# Motherboard.net
KiCad netlist of a schematic drawn in EAGLE
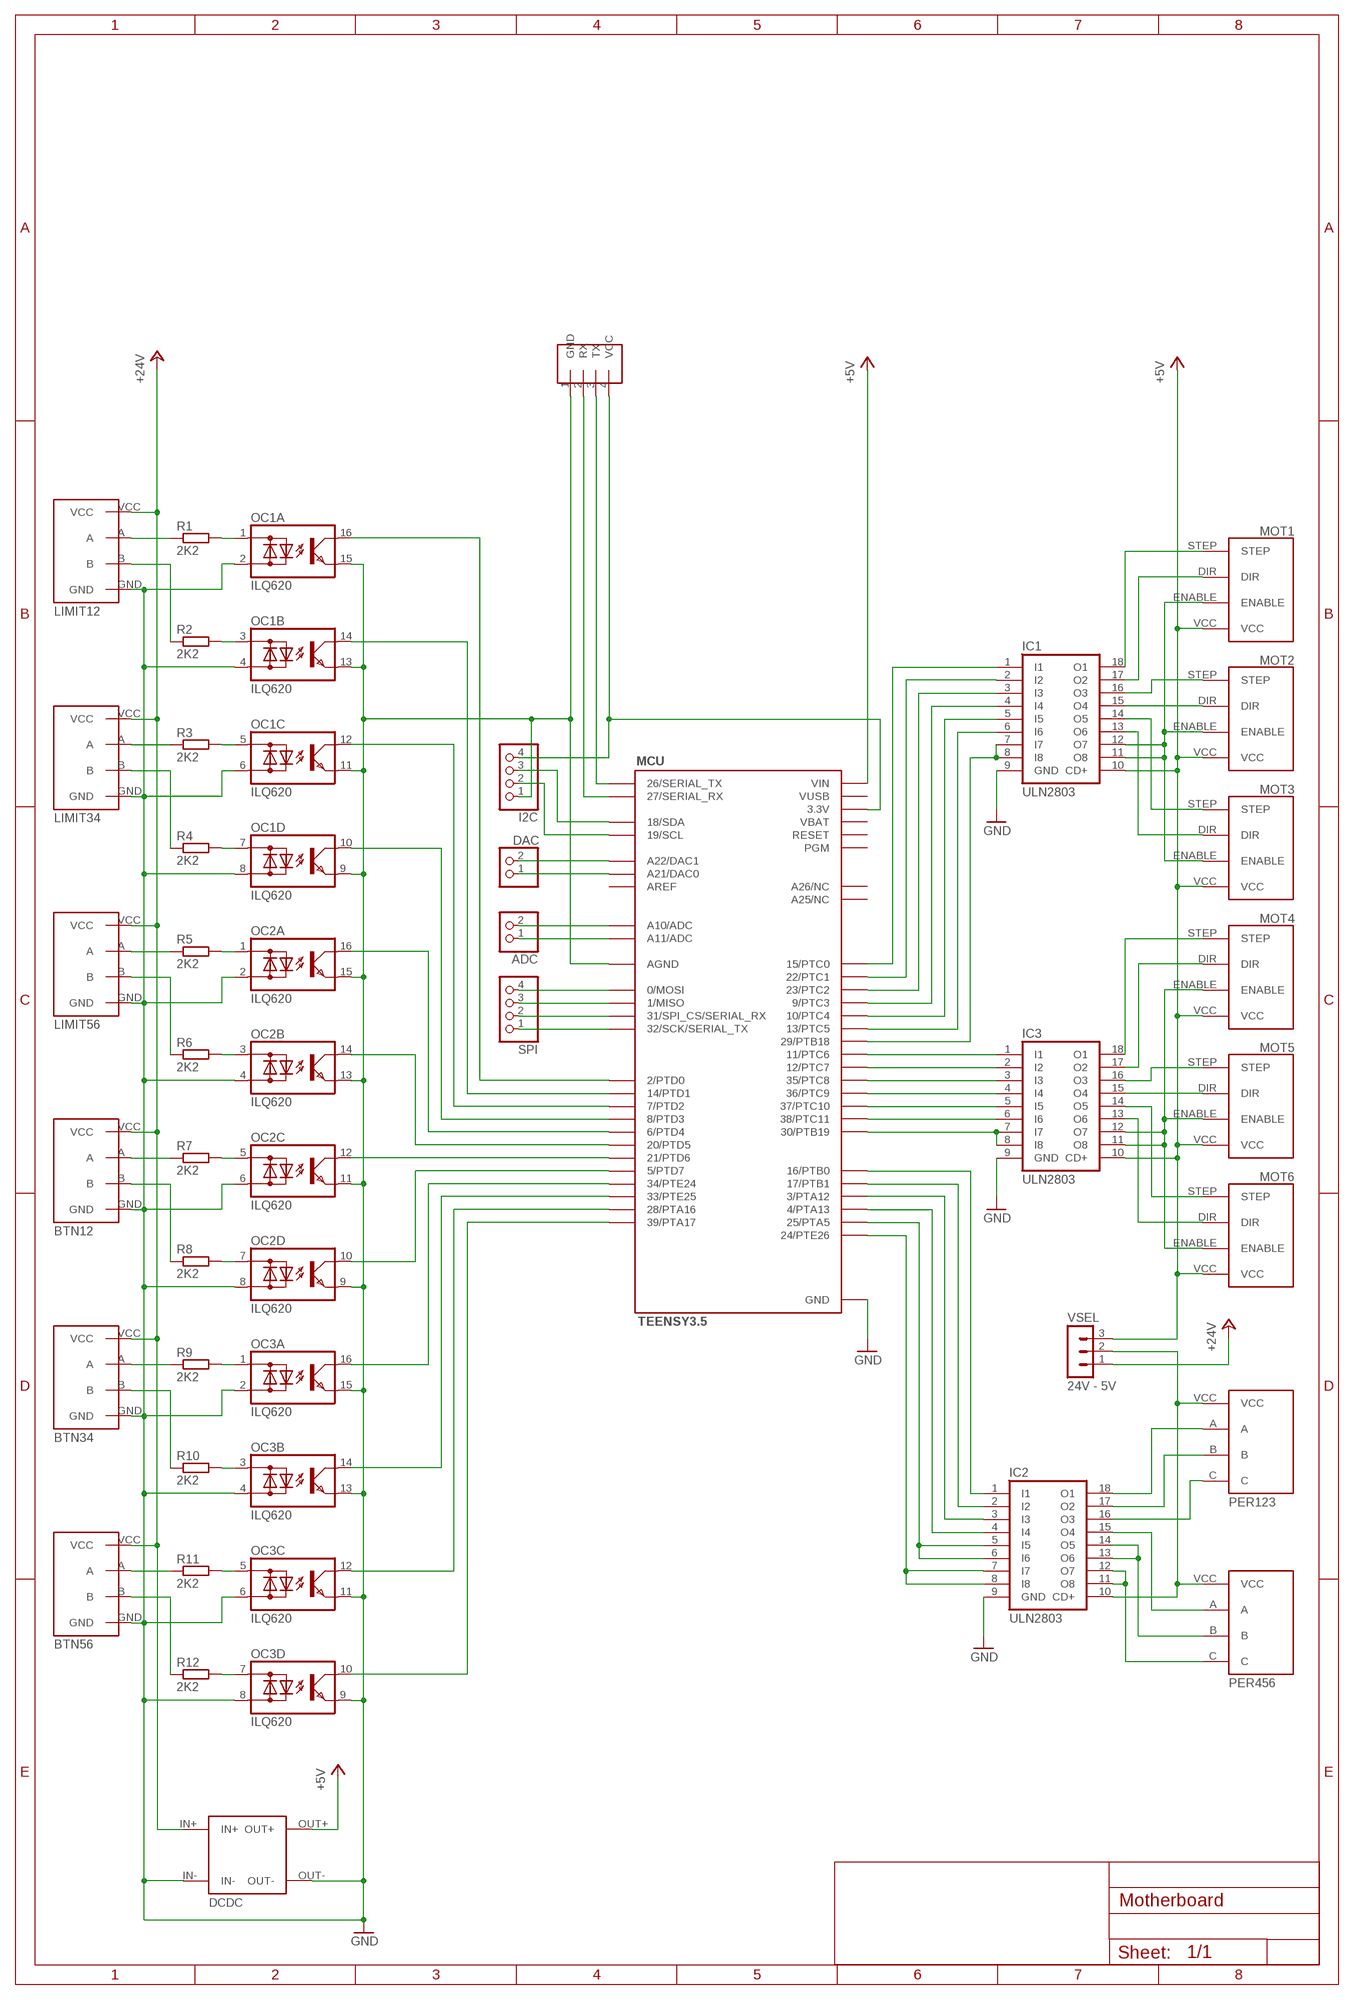
[diagram p0: schematic, sheet 1]

(export (version "E")
  (design (tool "Eeschema 10.0.6"))
  (components
    (comp (ref "ADC")
      (value "PINHD-1X2")
      (footprint "eagle-import:1X02")
      (libsource (lib "eagle-import") (part "PINHD-1X2"))
    )
    (comp (ref "BTN12")
      (value "CONN4B")
      (footprint "eagle-import:CONN4B")
      (libsource (lib "eagle-import") (part "CONN4B"))
    )
    (comp (ref "BTN34")
      (value "CONN4B")
      (footprint "eagle-import:CONN4B")
      (libsource (lib "eagle-import") (part "CONN4B"))
    )
    (comp (ref "BTN56")
      (value "CONN4B")
      (footprint "eagle-import:CONN4B")
      (libsource (lib "eagle-import") (part "CONN4B"))
    )
    (comp (ref "DAC")
      (value "PINHD-1X2")
      (footprint "eagle-import:1X02")
      (libsource (lib "eagle-import") (part "PINHD-1X2"))
    )
    (comp (ref "DCDC")
      (value "DCDC")
      (footprint "eagle-import:DCDC")
      (libsource (lib "eagle-import") (part "DCDC"))
    )
    (comp (ref "I2C")
      (value "PINHD-1X4")
      (footprint "eagle-import:1X04")
      (libsource (lib "eagle-import") (part "PINHD-1X4"))
    )
    (comp (ref "IC1")
      (value "ULN2803")
      (footprint "eagle-import:DIL18")
      (libsource (lib "eagle-import") (part "ULN2803A"))
    )
    (comp (ref "IC2")
      (value "ULN2803")
      (footprint "eagle-import:DIL18")
      (libsource (lib "eagle-import") (part "ULN2803A"))
    )
    (comp (ref "IC3")
      (value "ULN2803")
      (footprint "eagle-import:DIL18")
      (libsource (lib "eagle-import") (part "ULN2803A"))
    )
    (comp (ref "LIMIT12")
      (value "CONN4B")
      (footprint "eagle-import:CONN4B")
      (libsource (lib "eagle-import") (part "CONN4B"))
    )
    (comp (ref "LIMIT34")
      (value "CONN4B")
      (footprint "eagle-import:CONN4B")
      (libsource (lib "eagle-import") (part "CONN4B"))
    )
    (comp (ref "LIMIT56")
      (value "CONN4B")
      (footprint "eagle-import:CONN4B")
      (libsource (lib "eagle-import") (part "CONN4B"))
    )
    (comp (ref "MCU")
      (value "TEENSY3.5")
      (footprint "eagle-import:TEENSY_3.5_ALL_PINS")
      (libsource (lib "eagle-import") (part "TEENSY_3.5_ALL_PINS"))
    )
    (comp (ref "MOT1")
      (value "CONN4")
      (footprint "eagle-import:CONN4")
      (libsource (lib "eagle-import") (part "CONN4"))
    )
    (comp (ref "MOT2")
      (value "CONN4")
      (footprint "eagle-import:CONN4")
      (libsource (lib "eagle-import") (part "CONN4"))
    )
    (comp (ref "MOT3")
      (value "CONN4")
      (footprint "eagle-import:CONN4")
      (libsource (lib "eagle-import") (part "CONN4"))
    )
    (comp (ref "MOT4")
      (value "CONN4")
      (footprint "eagle-import:CONN4")
      (libsource (lib "eagle-import") (part "CONN4"))
    )
    (comp (ref "MOT5")
      (value "CONN4")
      (footprint "eagle-import:CONN4")
      (libsource (lib "eagle-import") (part "CONN4"))
    )
    (comp (ref "MOT6")
      (value "CONN4")
      (footprint "eagle-import:CONN4")
      (libsource (lib "eagle-import") (part "CONN4"))
    )
    (comp (ref "OC1")
      (value "ILQ620")
      (footprint "eagle-import:DIL16")
      (libsource (lib "eagle-import") (part "ILQ620"))
    )
    (comp (ref "OC2")
      (value "ILQ620")
      (footprint "eagle-import:DIL16")
      (libsource (lib "eagle-import") (part "ILQ620"))
    )
    (comp (ref "OC3")
      (value "ILQ620")
      (footprint "eagle-import:DIL16")
      (libsource (lib "eagle-import") (part "ILQ620"))
    )
    (comp (ref "PER123")
      (value "CONN4C")
      (footprint "eagle-import:CONN4C")
      (libsource (lib "eagle-import") (part "CONN4C"))
    )
    (comp (ref "PER456")
      (value "CONN4C")
      (footprint "eagle-import:CONN4C")
      (libsource (lib "eagle-import") (part "CONN4C"))
    )
    (comp (ref "R1")
      (value "2K2")
      (footprint "eagle-import:0207_10")
      (libsource (lib "eagle-import") (part "R-EU_0207/10"))
    )
    (comp (ref "R2")
      (value "2K2")
      (footprint "eagle-import:0207_10")
      (libsource (lib "eagle-import") (part "R-EU_0207/10"))
    )
    (comp (ref "R3")
      (value "2K2")
      (footprint "eagle-import:0207_10")
      (libsource (lib "eagle-import") (part "R-EU_0207/10"))
    )
    (comp (ref "R4")
      (value "2K2")
      (footprint "eagle-import:0207_10")
      (libsource (lib "eagle-import") (part "R-EU_0207/10"))
    )
    (comp (ref "R5")
      (value "2K2")
      (footprint "eagle-import:0207_10")
      (libsource (lib "eagle-import") (part "R-EU_0207/10"))
    )
    (comp (ref "R6")
      (value "2K2")
      (footprint "eagle-import:0207_10")
      (libsource (lib "eagle-import") (part "R-EU_0207/10"))
    )
    (comp (ref "R7")
      (value "2K2")
      (footprint "eagle-import:0207_10")
      (libsource (lib "eagle-import") (part "R-EU_0207/10"))
    )
    (comp (ref "R8")
      (value "2K2")
      (footprint "eagle-import:0207_10")
      (libsource (lib "eagle-import") (part "R-EU_0207/10"))
    )
    (comp (ref "R9")
      (value "2K2")
      (footprint "eagle-import:0207_10")
      (libsource (lib "eagle-import") (part "R-EU_0207/10"))
    )
    (comp (ref "R10")
      (value "2K2")
      (footprint "eagle-import:0207_10")
      (libsource (lib "eagle-import") (part "R-EU_0207/10"))
    )
    (comp (ref "R11")
      (value "2K2")
      (footprint "eagle-import:0207_10")
      (libsource (lib "eagle-import") (part "R-EU_0207/10"))
    )
    (comp (ref "R12")
      (value "2K2")
      (footprint "eagle-import:0207_10")
      (libsource (lib "eagle-import") (part "R-EU_0207/10"))
    )
    (comp (ref "SPI")
      (value "PINHD-1X4")
      (footprint "eagle-import:1X04")
      (libsource (lib "eagle-import") (part "PINHD-1X4"))
    )
    (comp (ref "U$1")
      (value "SERIAL-SUBD9-IF")
      (footprint "eagle-import:SERIAL-SUBD9-IF")
      (libsource (lib "eagle-import") (part "SERIAL-SUBD9-IF"))
    )
    (comp (ref "VSEL")
      (value "24V - 5V")
      (footprint "eagle-import:MA03-1")
      (libsource (lib "eagle-import") (part "MA03-1"))
    )
  )
  (nets
    (net (code "1") (name "+5V") (class "Default")
      (node (ref "DCDC") (pin "OUT+") (pinfunction "OUT+_OUT+") (pintype "power_in"))
      (node (ref "IC1") (pin "10") (pinfunction "CD+_10") (pintype "passive"))
      (node (ref "IC3") (pin "10") (pinfunction "CD+_10") (pintype "passive"))
      (node (ref "MCU") (pin "VIN") (pinfunction "VIN_VIN") (pintype "power_in"))
      (node (ref "MOT1") (pin "VCC") (pinfunction "VCC_VCC") (pintype "power_in"))
      (node (ref "MOT2") (pin "VCC") (pinfunction "VCC_VCC") (pintype "power_in"))
      (node (ref "MOT3") (pin "VCC") (pinfunction "VCC_VCC") (pintype "power_in"))
      (node (ref "MOT4") (pin "VCC") (pinfunction "VCC_VCC") (pintype "power_in"))
      (node (ref "MOT5") (pin "VCC") (pinfunction "VCC_VCC") (pintype "power_in"))
      (node (ref "MOT6") (pin "VCC") (pinfunction "VCC_VCC") (pintype "power_in"))
      (node (ref "VSEL") (pin "3") (pinfunction "3_3") (pintype "passive"))
    )
    (net (code "2") (name "+24V") (class "Default")
      (node (ref "BTN12") (pin "VCC") (pinfunction "VCC_VCC") (pintype "power_in"))
      (node (ref "BTN34") (pin "VCC") (pinfunction "VCC_VCC") (pintype "power_in"))
      (node (ref "BTN56") (pin "VCC") (pinfunction "VCC_VCC") (pintype "power_in"))
      (node (ref "DCDC") (pin "IN+") (pinfunction "IN+_IN+") (pintype "power_in"))
      (node (ref "LIMIT12") (pin "VCC") (pinfunction "VCC_VCC") (pintype "power_in"))
      (node (ref "LIMIT34") (pin "VCC") (pinfunction "VCC_VCC") (pintype "power_in"))
      (node (ref "LIMIT56") (pin "VCC") (pinfunction "VCC_VCC") (pintype "power_in"))
      (node (ref "VSEL") (pin "1") (pinfunction "1_1") (pintype "passive"))
    )
    (net (code "3") (name "/AREF") (class "Default")
      (node (ref "MCU") (pin "AREF") (pinfunction "AREF_AREF") (pintype "power_in"))
    )
    (net (code "4") (name "/VBAT") (class "Default")
      (node (ref "MCU") (pin "VBAT") (pinfunction "VBAT_VBAT") (pintype "power_in"))
    )
    (net (code "5") (name "/VUSB") (class "Default")
      (node (ref "MCU") (pin "VUSB") (pinfunction "VUSB_VUSB") (pintype "power_in"))
    )
    (net (code "6") (name "GND") (class "Default")
      (node (ref "BTN12") (pin "GND") (pinfunction "GND_GND") (pintype "power_in"))
      (node (ref "BTN34") (pin "GND") (pinfunction "GND_GND") (pintype "power_in"))
      (node (ref "BTN56") (pin "GND") (pinfunction "GND_GND") (pintype "power_in"))
      (node (ref "DCDC") (pin "IN-") (pinfunction "IN-_IN-") (pintype "power_in"))
      (node (ref "DCDC") (pin "OUT-") (pinfunction "OUT-_OUT-") (pintype "bidirectional"))
      (node (ref "I2C") (pin "1") (pinfunction "1_1") (pintype "passive"))
      (node (ref "IC1") (pin "9") (pinfunction "GND_9") (pintype "power_in"))
      (node (ref "IC2") (pin "9") (pinfunction "GND_9") (pintype "power_in"))
      (node (ref "IC3") (pin "9") (pinfunction "GND_9") (pintype "power_in"))
      (node (ref "LIMIT12") (pin "GND") (pinfunction "GND_GND") (pintype "power_in"))
      (node (ref "LIMIT34") (pin "GND") (pinfunction "GND_GND") (pintype "power_in"))
      (node (ref "LIMIT56") (pin "GND") (pinfunction "GND_GND") (pintype "power_in"))
      (node (ref "MCU") (pin "AGND") (pinfunction "AGND_AGND") (pintype "power_in"))
      (node (ref "MCU") (pin "GND") (pinfunction "GND_GND") (pintype "power_in"))
      (node (ref "MCU") (pin "GND1") (pinfunction "GND_GND1") (pintype "power_in"))
      (node (ref "MCU") (pin "GND3") (pinfunction "GND_GND3") (pintype "power_in"))
      (node (ref "MCU") (pin "GND4") (pinfunction "GND_GND4") (pintype "power_in"))
      (node (ref "MCU") (pin "GND6") (pinfunction "GND_GND6") (pintype "power_in"))
      (node (ref "OC1") (pin "11") (pinfunction "E_11") (pintype "passive"))
      (node (ref "OC1") (pin "13") (pinfunction "E_13") (pintype "passive"))
      (node (ref "OC1") (pin "15") (pinfunction "E_15") (pintype "passive"))
      (node (ref "OC1") (pin "2") (pinfunction "AC2_2") (pintype "passive"))
      (node (ref "OC1") (pin "4") (pinfunction "AC2_4") (pintype "passive"))
      (node (ref "OC1") (pin "6") (pinfunction "AC2_6") (pintype "passive"))
      (node (ref "OC1") (pin "8") (pinfunction "AC2_8") (pintype "passive"))
      (node (ref "OC1") (pin "9") (pinfunction "E_9") (pintype "passive"))
      (node (ref "OC2") (pin "11") (pinfunction "E_11") (pintype "passive"))
      (node (ref "OC2") (pin "13") (pinfunction "E_13") (pintype "passive"))
      (node (ref "OC2") (pin "15") (pinfunction "E_15") (pintype "passive"))
      (node (ref "OC2") (pin "2") (pinfunction "AC2_2") (pintype "passive"))
      (node (ref "OC2") (pin "4") (pinfunction "AC2_4") (pintype "passive"))
      (node (ref "OC2") (pin "6") (pinfunction "AC2_6") (pintype "passive"))
      (node (ref "OC2") (pin "8") (pinfunction "AC2_8") (pintype "passive"))
      (node (ref "OC2") (pin "9") (pinfunction "E_9") (pintype "passive"))
      (node (ref "OC3") (pin "11") (pinfunction "E_11") (pintype "passive"))
      (node (ref "OC3") (pin "13") (pinfunction "E_13") (pintype "passive"))
      (node (ref "OC3") (pin "15") (pinfunction "E_15") (pintype "passive"))
      (node (ref "OC3") (pin "2") (pinfunction "AC2_2") (pintype "passive"))
      (node (ref "OC3") (pin "4") (pinfunction "AC2_4") (pintype "passive"))
      (node (ref "OC3") (pin "6") (pinfunction "AC2_6") (pintype "passive"))
      (node (ref "OC3") (pin "8") (pinfunction "AC2_8") (pintype "passive"))
      (node (ref "OC3") (pin "9") (pinfunction "E_9") (pintype "passive"))
      (node (ref "U$1") (pin "1") (pinfunction "GND_1") (pintype "power_in"))
    )
    (net (code "7") (name "Net-(BTN12-PadA)") (class "Default")
      (node (ref "BTN12") (pin "A") (pinfunction "A_A") (pintype "bidirectional"))
      (node (ref "R7") (pin "1") (pinfunction "1_1") (pintype "passive"))
    )
    (net (code "8") (name "Net-(BTN12-PadB)") (class "Default")
      (node (ref "BTN12") (pin "B") (pinfunction "B_B") (pintype "bidirectional"))
      (node (ref "R8") (pin "1") (pinfunction "1_1") (pintype "passive"))
    )
    (net (code "9") (name "Net-(BTN34-PadA)") (class "Default")
      (node (ref "BTN34") (pin "A") (pinfunction "A_A") (pintype "bidirectional"))
      (node (ref "R9") (pin "1") (pinfunction "1_1") (pintype "passive"))
    )
    (net (code "10") (name "Net-(BTN34-PadB)") (class "Default")
      (node (ref "BTN34") (pin "B") (pinfunction "B_B") (pintype "bidirectional"))
      (node (ref "R10") (pin "1") (pinfunction "1_1") (pintype "passive"))
    )
    (net (code "11") (name "Net-(BTN56-PadA)") (class "Default")
      (node (ref "BTN56") (pin "A") (pinfunction "A_A") (pintype "bidirectional"))
      (node (ref "R11") (pin "1") (pinfunction "1_1") (pintype "passive"))
    )
    (net (code "12") (name "Net-(BTN56-PadB)") (class "Default")
      (node (ref "BTN56") (pin "B") (pinfunction "B_B") (pintype "bidirectional"))
      (node (ref "R12") (pin "1") (pinfunction "1_1") (pintype "passive"))
    )
    (net (code "13") (name "Net-(IC1-I1)") (class "Default")
      (node (ref "IC1") (pin "1") (pinfunction "I1_1") (pintype "input"))
      (node (ref "MCU") (pin "15/A1") (pinfunction "15/PTC0_15/A1") (pintype "bidirectional"))
    )
    (net (code "14") (name "Net-(IC1-I2)") (class "Default")
      (node (ref "IC1") (pin "2") (pinfunction "I2_2") (pintype "input"))
      (node (ref "MCU") (pin "22/A8") (pinfunction "22/PTC1_22/A8") (pintype "bidirectional"))
    )
    (net (code "15") (name "Net-(IC1-I3)") (class "Default")
      (node (ref "IC1") (pin "3") (pinfunction "I3_3") (pintype "input"))
      (node (ref "MCU") (pin "23/A9") (pinfunction "23/PTC2_23/A9") (pintype "bidirectional"))
    )
    (net (code "16") (name "Net-(IC1-I4)") (class "Default")
      (node (ref "IC1") (pin "4") (pinfunction "I4_4") (pintype "input"))
      (node (ref "MCU") (pin "9") (pinfunction "9/PTC3_9") (pintype "bidirectional"))
    )
    (net (code "17") (name "Net-(IC1-I5)") (class "Default")
      (node (ref "IC1") (pin "5") (pinfunction "I5_5") (pintype "input"))
      (node (ref "MCU") (pin "10") (pinfunction "10/PTC4_10") (pintype "bidirectional"))
    )
    (net (code "18") (name "Net-(IC1-I6)") (class "Default")
      (node (ref "IC1") (pin "6") (pinfunction "I6_6") (pintype "input"))
      (node (ref "MCU") (pin "13") (pinfunction "13/PTC5_13") (pintype "bidirectional"))
    )
    (net (code "19") (name "Net-(IC1-I7)") (class "Default")
      (node (ref "IC1") (pin "7") (pinfunction "I7_7") (pintype "input"))
      (node (ref "IC1") (pin "8") (pinfunction "I8_8") (pintype "input"))
      (node (ref "MCU") (pin "29") (pinfunction "29/PTB18_29") (pintype "bidirectional"))
    )
    (net (code "20") (name "Net-(IC1-O1)") (class "Default")
      (node (ref "IC1") (pin "18") (pinfunction "O1_18") (pintype "open_collector"))
      (node (ref "MOT1") (pin "STEP") (pinfunction "STEP_STEP") (pintype "bidirectional"))
    )
    (net (code "21") (name "Net-(IC1-O2)") (class "Default")
      (node (ref "IC1") (pin "17") (pinfunction "O2_17") (pintype "open_collector"))
      (node (ref "MOT1") (pin "DIR") (pinfunction "DIR_DIR") (pintype "bidirectional"))
    )
    (net (code "22") (name "Net-(IC1-O3)") (class "Default")
      (node (ref "IC1") (pin "16") (pinfunction "O3_16") (pintype "open_collector"))
      (node (ref "MOT2") (pin "STEP") (pinfunction "STEP_STEP") (pintype "bidirectional"))
    )
    (net (code "23") (name "Net-(IC1-O4)") (class "Default")
      (node (ref "IC1") (pin "15") (pinfunction "O4_15") (pintype "open_collector"))
      (node (ref "MOT2") (pin "DIR") (pinfunction "DIR_DIR") (pintype "bidirectional"))
    )
    (net (code "24") (name "Net-(IC1-O5)") (class "Default")
      (node (ref "IC1") (pin "14") (pinfunction "O5_14") (pintype "open_collector"))
      (node (ref "MOT3") (pin "STEP") (pinfunction "STEP_STEP") (pintype "bidirectional"))
    )
    (net (code "25") (name "Net-(IC1-O6)") (class "Default")
      (node (ref "IC1") (pin "13") (pinfunction "O6_13") (pintype "open_collector"))
      (node (ref "MOT3") (pin "DIR") (pinfunction "DIR_DIR") (pintype "bidirectional"))
    )
    (net (code "26") (name "Net-(IC1-O7)") (class "Default")
      (node (ref "IC1") (pin "11") (pinfunction "O8_11") (pintype "open_collector"))
      (node (ref "IC1") (pin "12") (pinfunction "O7_12") (pintype "open_collector"))
      (node (ref "MOT1") (pin "ENABLE") (pinfunction "ENABLE_ENABLE") (pintype "bidirectional"))
      (node (ref "MOT2") (pin "ENABLE") (pinfunction "ENABLE_ENABLE") (pintype "bidirectional"))
      (node (ref "MOT3") (pin "ENABLE") (pinfunction "ENABLE_ENABLE") (pintype "bidirectional"))
    )
    (net (code "27") (name "Net-(IC2-CD+)") (class "Default")
      (node (ref "IC2") (pin "10") (pinfunction "CD+_10") (pintype "passive"))
      (node (ref "PER123") (pin "VCC") (pinfunction "VCC_VCC") (pintype "power_in"))
      (node (ref "PER456") (pin "VCC") (pinfunction "VCC_VCC") (pintype "power_in"))
      (node (ref "VSEL") (pin "2") (pinfunction "2_2") (pintype "passive"))
    )
    (net (code "28") (name "Net-(IC2-I1)") (class "Default")
      (node (ref "IC2") (pin "1") (pinfunction "I1_1") (pintype "input"))
      (node (ref "MCU") (pin "16/A2") (pinfunction "16/PTB0_16/A2") (pintype "bidirectional"))
    )
    (net (code "29") (name "Net-(IC2-I2)") (class "Default")
      (node (ref "IC2") (pin "2") (pinfunction "I2_2") (pintype "input"))
      (node (ref "MCU") (pin "17/A3") (pinfunction "17/PTB1_17/A3") (pintype "bidirectional"))
    )
    (net (code "30") (name "Net-(IC2-I3)") (class "Default")
      (node (ref "IC2") (pin "3") (pinfunction "I3_3") (pintype "input"))
      (node (ref "MCU") (pin "3") (pinfunction "3/PTA12_3") (pintype "bidirectional"))
    )
    (net (code "31") (name "Net-(IC2-I4)") (class "Default")
      (node (ref "IC2") (pin "4") (pinfunction "I4_4") (pintype "input"))
      (node (ref "MCU") (pin "4") (pinfunction "4/PTA13_4") (pintype "bidirectional"))
    )
    (net (code "32") (name "Net-(IC2-I5)") (class "Default")
      (node (ref "IC2") (pin "5") (pinfunction "I5_5") (pintype "input"))
      (node (ref "IC2") (pin "6") (pinfunction "I6_6") (pintype "input"))
      (node (ref "MCU") (pin "25") (pinfunction "25/PTA5_25") (pintype "bidirectional"))
    )
    (net (code "33") (name "Net-(IC2-I7)") (class "Default")
      (node (ref "IC2") (pin "7") (pinfunction "I7_7") (pintype "input"))
      (node (ref "IC2") (pin "8") (pinfunction "I8_8") (pintype "input"))
      (node (ref "MCU") (pin "24") (pinfunction "24/PTE26_24") (pintype "bidirectional"))
    )
    (net (code "34") (name "Net-(IC2-O1)") (class "Default")
      (node (ref "IC2") (pin "18") (pinfunction "O1_18") (pintype "open_collector"))
      (node (ref "PER123") (pin "A") (pinfunction "A_A") (pintype "bidirectional"))
    )
    (net (code "35") (name "Net-(IC2-O2)") (class "Default")
      (node (ref "IC2") (pin "17") (pinfunction "O2_17") (pintype "open_collector"))
      (node (ref "PER123") (pin "B") (pinfunction "B_B") (pintype "bidirectional"))
    )
    (net (code "36") (name "Net-(IC2-O3)") (class "Default")
      (node (ref "IC2") (pin "16") (pinfunction "O3_16") (pintype "open_collector"))
      (node (ref "PER123") (pin "C") (pinfunction "C_C") (pintype "bidirectional"))
    )
    (net (code "37") (name "Net-(IC2-O4)") (class "Default")
      (node (ref "IC2") (pin "15") (pinfunction "O4_15") (pintype "open_collector"))
      (node (ref "PER456") (pin "A") (pinfunction "A_A") (pintype "bidirectional"))
    )
    (net (code "38") (name "Net-(IC2-O5)") (class "Default")
      (node (ref "IC2") (pin "13") (pinfunction "O6_13") (pintype "open_collector"))
      (node (ref "IC2") (pin "14") (pinfunction "O5_14") (pintype "open_collector"))
      (node (ref "PER456") (pin "B") (pinfunction "B_B") (pintype "bidirectional"))
    )
    (net (code "39") (name "Net-(IC2-O7)") (class "Default")
      (node (ref "IC2") (pin "11") (pinfunction "O8_11") (pintype "open_collector"))
      (node (ref "IC2") (pin "12") (pinfunction "O7_12") (pintype "open_collector"))
      (node (ref "PER456") (pin "C") (pinfunction "C_C") (pintype "bidirectional"))
    )
    (net (code "40") (name "Net-(IC3-I1)") (class "Default")
      (node (ref "IC3") (pin "1") (pinfunction "I1_1") (pintype "input"))
      (node (ref "MCU") (pin "11") (pinfunction "11/PTC6_11") (pintype "bidirectional"))
    )
    (net (code "41") (name "Net-(IC3-I2)") (class "Default")
      (node (ref "IC3") (pin "2") (pinfunction "I2_2") (pintype "input"))
      (node (ref "MCU") (pin "12") (pinfunction "12/PTC7_12") (pintype "bidirectional"))
    )
    (net (code "42") (name "Net-(IC3-I3)") (class "Default")
      (node (ref "IC3") (pin "3") (pinfunction "I3_3") (pintype "input"))
      (node (ref "MCU") (pin "35/A16") (pinfunction "35/PTC8_35/A16") (pintype "bidirectional"))
    )
    (net (code "43") (name "Net-(IC3-I4)") (class "Default")
      (node (ref "IC3") (pin "4") (pinfunction "I4_4") (pintype "input"))
      (node (ref "MCU") (pin "36/A17") (pinfunction "36/PTC9_36/A17") (pintype "bidirectional"))
    )
    (net (code "44") (name "Net-(IC3-I5)") (class "Default")
      (node (ref "IC3") (pin "5") (pinfunction "I5_5") (pintype "input"))
      (node (ref "MCU") (pin "37/A18") (pinfunction "37/PTC10_37/A18") (pintype "bidirectional"))
    )
    (net (code "45") (name "Net-(IC3-I6)") (class "Default")
      (node (ref "IC3") (pin "6") (pinfunction "I6_6") (pintype "input"))
      (node (ref "MCU") (pin "38/A19") (pinfunction "38/PTC11_38/A19") (pintype "bidirectional"))
    )
    (net (code "46") (name "Net-(IC3-I7)") (class "Default")
      (node (ref "IC3") (pin "7") (pinfunction "I7_7") (pintype "input"))
      (node (ref "IC3") (pin "8") (pinfunction "I8_8") (pintype "input"))
      (node (ref "MCU") (pin "30") (pinfunction "30/PTB19_30") (pintype "bidirectional"))
    )
    (net (code "47") (name "Net-(IC3-O1)") (class "Default")
      (node (ref "IC3") (pin "18") (pinfunction "O1_18") (pintype "open_collector"))
      (node (ref "MOT4") (pin "STEP") (pinfunction "STEP_STEP") (pintype "bidirectional"))
    )
    (net (code "48") (name "Net-(IC3-O2)") (class "Default")
      (node (ref "IC3") (pin "17") (pinfunction "O2_17") (pintype "open_collector"))
      (node (ref "MOT4") (pin "DIR") (pinfunction "DIR_DIR") (pintype "bidirectional"))
    )
    (net (code "49") (name "Net-(IC3-O3)") (class "Default")
      (node (ref "IC3") (pin "16") (pinfunction "O3_16") (pintype "open_collector"))
      (node (ref "MOT5") (pin "STEP") (pinfunction "STEP_STEP") (pintype "bidirectional"))
    )
    (net (code "50") (name "Net-(IC3-O4)") (class "Default")
      (node (ref "IC3") (pin "15") (pinfunction "O4_15") (pintype "open_collector"))
      (node (ref "MOT5") (pin "DIR") (pinfunction "DIR_DIR") (pintype "bidirectional"))
    )
    (net (code "51") (name "Net-(IC3-O5)") (class "Default")
      (node (ref "IC3") (pin "14") (pinfunction "O5_14") (pintype "open_collector"))
      (node (ref "MOT6") (pin "STEP") (pinfunction "STEP_STEP") (pintype "bidirectional"))
    )
    (net (code "52") (name "Net-(IC3-O6)") (class "Default")
      (node (ref "IC3") (pin "13") (pinfunction "O6_13") (pintype "open_collector"))
      (node (ref "MOT6") (pin "DIR") (pinfunction "DIR_DIR") (pintype "bidirectional"))
    )
    (net (code "53") (name "Net-(IC3-O7)") (class "Default")
      (node (ref "IC3") (pin "11") (pinfunction "O8_11") (pintype "open_collector"))
      (node (ref "IC3") (pin "12") (pinfunction "O7_12") (pintype "open_collector"))
      (node (ref "MOT4") (pin "ENABLE") (pinfunction "ENABLE_ENABLE") (pintype "bidirectional"))
      (node (ref "MOT5") (pin "ENABLE") (pinfunction "ENABLE_ENABLE") (pintype "bidirectional"))
      (node (ref "MOT6") (pin "ENABLE") (pinfunction "ENABLE_ENABLE") (pintype "bidirectional"))
    )
    (net (code "54") (name "Net-(LIMIT12-PadA)") (class "Default")
      (node (ref "LIMIT12") (pin "A") (pinfunction "A_A") (pintype "bidirectional"))
      (node (ref "R1") (pin "1") (pinfunction "1_1") (pintype "passive"))
    )
    (net (code "55") (name "Net-(LIMIT12-PadB)") (class "Default")
      (node (ref "LIMIT12") (pin "B") (pinfunction "B_B") (pintype "bidirectional"))
      (node (ref "R2") (pin "1") (pinfunction "1_1") (pintype "passive"))
    )
    (net (code "56") (name "Net-(LIMIT34-PadA)") (class "Default")
      (node (ref "LIMIT34") (pin "A") (pinfunction "A_A") (pintype "bidirectional"))
      (node (ref "R3") (pin "1") (pinfunction "1_1") (pintype "passive"))
    )
    (net (code "57") (name "Net-(LIMIT34-PadB)") (class "Default")
      (node (ref "LIMIT34") (pin "B") (pinfunction "B_B") (pintype "bidirectional"))
      (node (ref "R4") (pin "1") (pinfunction "1_1") (pintype "passive"))
    )
    (net (code "58") (name "Net-(LIMIT56-PadA)") (class "Default")
      (node (ref "LIMIT56") (pin "A") (pinfunction "A_A") (pintype "bidirectional"))
      (node (ref "R5") (pin "1") (pinfunction "1_1") (pintype "passive"))
    )
    (net (code "59") (name "Net-(LIMIT56-PadB)") (class "Default")
      (node (ref "LIMIT56") (pin "B") (pinfunction "B_B") (pintype "bidirectional"))
      (node (ref "R6") (pin "1") (pinfunction "1_1") (pintype "passive"))
    )
    (net (code "60") (name "Net-(MCU-0{slash}MOSI)") (class "Default")
      (node (ref "MCU") (pin "0") (pinfunction "0/MOSI_0") (pintype "bidirectional"))
      (node (ref "SPI") (pin "4") (pinfunction "4_4") (pintype "passive"))
    )
    (net (code "61") (name "Net-(MCU-1{slash}MISO)") (class "Default")
      (node (ref "MCU") (pin "1") (pinfunction "1/MISO_1") (pintype "bidirectional"))
      (node (ref "SPI") (pin "3") (pinfunction "3_3") (pintype "passive"))
    )
    (net (code "62") (name "Net-(MCU-2{slash}PTD0)") (class "Default")
      (node (ref "MCU") (pin "2") (pinfunction "2/PTD0_2") (pintype "bidirectional"))
      (node (ref "OC1") (pin "16") (pinfunction "C_16") (pintype "passive"))
    )
    (net (code "63") (name "Net-(MCU-5{slash}PTD7)") (class "Default")
      (node (ref "MCU") (pin "5") (pinfunction "5/PTD7_5") (pintype "bidirectional"))
      (node (ref "OC2") (pin "10") (pinfunction "C_10") (pintype "passive"))
    )
    (net (code "64") (name "Net-(MCU-6{slash}PTD4)") (class "Default")
      (node (ref "MCU") (pin "6") (pinfunction "6/PTD4_6") (pintype "bidirectional"))
      (node (ref "OC2") (pin "16") (pinfunction "C_16") (pintype "passive"))
    )
    (net (code "65") (name "Net-(MCU-7{slash}PTD2)") (class "Default")
      (node (ref "MCU") (pin "7") (pinfunction "7/PTD2_7") (pintype "bidirectional"))
      (node (ref "OC1") (pin "12") (pinfunction "C_12") (pintype "passive"))
    )
    (net (code "66") (name "Net-(MCU-8{slash}PTD3)") (class "Default")
      (node (ref "MCU") (pin "8") (pinfunction "8/PTD3_8") (pintype "bidirectional"))
      (node (ref "OC1") (pin "10") (pinfunction "C_10") (pintype "passive"))
    )
    (net (code "67") (name "Net-(MCU-14{slash}PTD1)") (class "Default")
      (node (ref "MCU") (pin "14/A0") (pinfunction "14/PTD1_14/A0") (pintype "bidirectional"))
      (node (ref "OC1") (pin "14") (pinfunction "C_14") (pintype "passive"))
    )
    (net (code "68") (name "Net-(MCU-18{slash}SDA)") (class "Default")
      (node (ref "I2C") (pin "3") (pinfunction "3_3") (pintype "passive"))
      (node (ref "MCU") (pin "18/A4") (pinfunction "18/SDA_18/A4") (pintype "bidirectional"))
    )
    (net (code "69") (name "Net-(MCU-19{slash}SCL)") (class "Default")
      (node (ref "I2C") (pin "2") (pinfunction "2_2") (pintype "passive"))
      (node (ref "MCU") (pin "19/A5") (pinfunction "19/SCL_19/A5") (pintype "bidirectional"))
    )
    (net (code "70") (name "Net-(MCU-20{slash}PTD5)") (class "Default")
      (node (ref "MCU") (pin "20/A6") (pinfunction "20/PTD5_20/A6") (pintype "bidirectional"))
      (node (ref "OC2") (pin "14") (pinfunction "C_14") (pintype "passive"))
    )
    (net (code "71") (name "Net-(MCU-21{slash}PTD6)") (class "Default")
      (node (ref "MCU") (pin "21/A7") (pinfunction "21/PTD6_21/A7") (pintype "bidirectional"))
      (node (ref "OC2") (pin "12") (pinfunction "C_12") (pintype "passive"))
    )
    (net (code "72") (name "Net-(MCU-26{slash}SERIAL_TX)") (class "Default")
      (node (ref "MCU") (pin "26") (pinfunction "26/SERIAL_TX_26") (pintype "bidirectional"))
      (node (ref "U$1") (pin "3") (pinfunction "TX_3") (pintype "bidirectional"))
    )
    (net (code "73") (name "Net-(MCU-27{slash}SERIAL_RX)") (class "Default")
      (node (ref "MCU") (pin "27") (pinfunction "27/SERIAL_RX_27") (pintype "bidirectional"))
      (node (ref "U$1") (pin "2") (pinfunction "RX_2") (pintype "bidirectional"))
    )
    (net (code "74") (name "Net-(MCU-28{slash}PTA16)") (class "Default")
      (node (ref "MCU") (pin "28") (pinfunction "28/PTA16_28") (pintype "bidirectional"))
      (node (ref "OC3") (pin "12") (pinfunction "C_12") (pintype "passive"))
    )
    (net (code "75") (name "Net-(MCU-31{slash}SPI_CS{slash}SERIAL_RX)") (class "Default")
      (node (ref "MCU") (pin "31/A12") (pinfunction "31/SPI_CS/SERIAL_RX_31/A12") (pintype "bidirectional"))
      (node (ref "SPI") (pin "2") (pinfunction "2_2") (pintype "passive"))
    )
    (net (code "76") (name "Net-(MCU-32{slash}SCK{slash}SERIAL_TX)") (class "Default")
      (node (ref "MCU") (pin "32/A13") (pinfunction "32/SCK/SERIAL_TX_32/A13") (pintype "bidirectional"))
      (node (ref "SPI") (pin "1") (pinfunction "1_1") (pintype "passive"))
    )
    (net (code "77") (name "Net-(MCU-33{slash}PTE25)") (class "Default")
      (node (ref "MCU") (pin "33/A14") (pinfunction "33/PTE25_33/A14") (pintype "bidirectional"))
      (node (ref "OC3") (pin "14") (pinfunction "C_14") (pintype "passive"))
    )
    (net (code "78") (name "Net-(MCU-34{slash}PTE24)") (class "Default")
      (node (ref "MCU") (pin "34/A15") (pinfunction "34/PTE24_34/A15") (pintype "bidirectional"))
      (node (ref "OC3") (pin "16") (pinfunction "C_16") (pintype "passive"))
    )
    (net (code "79") (name "Net-(MCU-39{slash}PTA17)") (class "Default")
      (node (ref "MCU") (pin "39/A20") (pinfunction "39/PTA17_39/A20") (pintype "bidirectional"))
      (node (ref "OC3") (pin "10") (pinfunction "C_10") (pintype "passive"))
    )
    (net (code "80") (name "Net-(MCU-A10{slash}ADC)") (class "Default")
      (node (ref "ADC") (pin "2") (pinfunction "2_2") (pintype "passive"))
      (node (ref "MCU") (pin "A10") (pinfunction "A10/ADC_A10") (pintype "bidirectional"))
    )
    (net (code "81") (name "Net-(MCU-A11{slash}ADC)") (class "Default")
      (node (ref "ADC") (pin "1") (pinfunction "1_1") (pintype "passive"))
      (node (ref "MCU") (pin "A11") (pinfunction "A11/ADC_A11") (pintype "bidirectional"))
    )
    (net (code "82") (name "Net-(MCU-A21{slash}DAC0)") (class "Default")
      (node (ref "DAC") (pin "1") (pinfunction "1_1") (pintype "passive"))
      (node (ref "MCU") (pin "A21") (pinfunction "A21/DAC0_A21") (pintype "bidirectional"))
    )
    (net (code "83") (name "Net-(MCU-A22{slash}DAC1)") (class "Default")
      (node (ref "DAC") (pin "2") (pinfunction "2_2") (pintype "passive"))
      (node (ref "MCU") (pin "A22") (pinfunction "A22/DAC1_A22") (pintype "bidirectional"))
    )
    (net (code "84") (name "Net-(OC1A-AC1)") (class "Default")
      (node (ref "OC1") (pin "1") (pinfunction "AC1_1") (pintype "passive"))
      (node (ref "R1") (pin "2") (pinfunction "2_2") (pintype "passive"))
    )
    (net (code "85") (name "Net-(OC1B-AC1)") (class "Default")
      (node (ref "OC1") (pin "3") (pinfunction "AC1_3") (pintype "passive"))
      (node (ref "R2") (pin "2") (pinfunction "2_2") (pintype "passive"))
    )
    (net (code "86") (name "Net-(OC1C-AC1)") (class "Default")
      (node (ref "OC1") (pin "5") (pinfunction "AC1_5") (pintype "passive"))
      (node (ref "R3") (pin "2") (pinfunction "2_2") (pintype "passive"))
    )
    (net (code "87") (name "Net-(OC1D-AC1)") (class "Default")
      (node (ref "OC1") (pin "7") (pinfunction "AC1_7") (pintype "passive"))
      (node (ref "R4") (pin "2") (pinfunction "2_2") (pintype "passive"))
    )
    (net (code "88") (name "Net-(OC2A-AC1)") (class "Default")
      (node (ref "OC2") (pin "1") (pinfunction "AC1_1") (pintype "passive"))
      (node (ref "R5") (pin "2") (pinfunction "2_2") (pintype "passive"))
    )
    (net (code "89") (name "Net-(OC2B-AC1)") (class "Default")
      (node (ref "OC2") (pin "3") (pinfunction "AC1_3") (pintype "passive"))
      (node (ref "R6") (pin "2") (pinfunction "2_2") (pintype "passive"))
    )
    (net (code "90") (name "Net-(OC2C-AC1)") (class "Default")
      (node (ref "OC2") (pin "5") (pinfunction "AC1_5") (pintype "passive"))
      (node (ref "R7") (pin "2") (pinfunction "2_2") (pintype "passive"))
    )
    (net (code "91") (name "Net-(OC2D-AC1)") (class "Default")
      (node (ref "OC2") (pin "7") (pinfunction "AC1_7") (pintype "passive"))
      (node (ref "R8") (pin "2") (pinfunction "2_2") (pintype "passive"))
    )
    (net (code "92") (name "Net-(OC3A-AC1)") (class "Default")
      (node (ref "OC3") (pin "1") (pinfunction "AC1_1") (pintype "passive"))
      (node (ref "R9") (pin "2") (pinfunction "2_2") (pintype "passive"))
    )
    (net (code "93") (name "Net-(OC3B-AC1)") (class "Default")
      (node (ref "OC3") (pin "3") (pinfunction "AC1_3") (pintype "passive"))
      (node (ref "R10") (pin "2") (pinfunction "2_2") (pintype "passive"))
    )
    (net (code "94") (name "Net-(OC3C-AC1)") (class "Default")
      (node (ref "OC3") (pin "5") (pinfunction "AC1_5") (pintype "passive"))
      (node (ref "R11") (pin "2") (pinfunction "2_2") (pintype "passive"))
    )
    (net (code "95") (name "Net-(OC3D-AC1)") (class "Default")
      (node (ref "OC3") (pin "7") (pinfunction "AC1_7") (pintype "passive"))
      (node (ref "R12") (pin "2") (pinfunction "2_2") (pintype "passive"))
    )
    (net (code "96") (name "Net-(U$1-VCC)") (class "Default")
      (node (ref "I2C") (pin "4") (pinfunction "4_4") (pintype "passive"))
      (node (ref "MCU") (pin "3.3V") (pinfunction "3.3V_3.3V") (pintype "power_in"))
      (node (ref "MCU") (pin "3.3V3") (pinfunction "3.3V_3.3V3") (pintype "power_in"))
      (node (ref "MCU") (pin "3.3V4") (pinfunction "3.3V_3.3V4") (pintype "power_in"))
      (node (ref "U$1") (pin "4") (pinfunction "VCC_4") (pintype "power_in"))
    )
    (net (code "97") (name "unconnected-(MCU-A25{slash}NC-PadA25)") (class "Default")
      (node (ref "MCU") (pin "A25") (pinfunction "A25/NC_A25") (pintype "bidirectional"))
    )
    (net (code "98") (name "unconnected-(MCU-A26{slash}NC-PadA26)") (class "Default")
      (node (ref "MCU") (pin "A26") (pinfunction "A26/NC_A26") (pintype "bidirectional"))
    )
    (net (code "99") (name "unconnected-(MCU-PadPGM)") (class "Default")
      (node (ref "MCU") (pin "PGM") (pinfunction "PGM_PGM") (pintype "bidirectional"))
    )
    (net (code "100") (name "unconnected-(MCU-PadRESET)") (class "Default")
      (node (ref "MCU") (pin "RESET") (pinfunction "RESET_RESET") (pintype "bidirectional"))
    )
  )
)
